# bootloader_burner.net
KiCad netlist of a schematic drawn in EAGLE
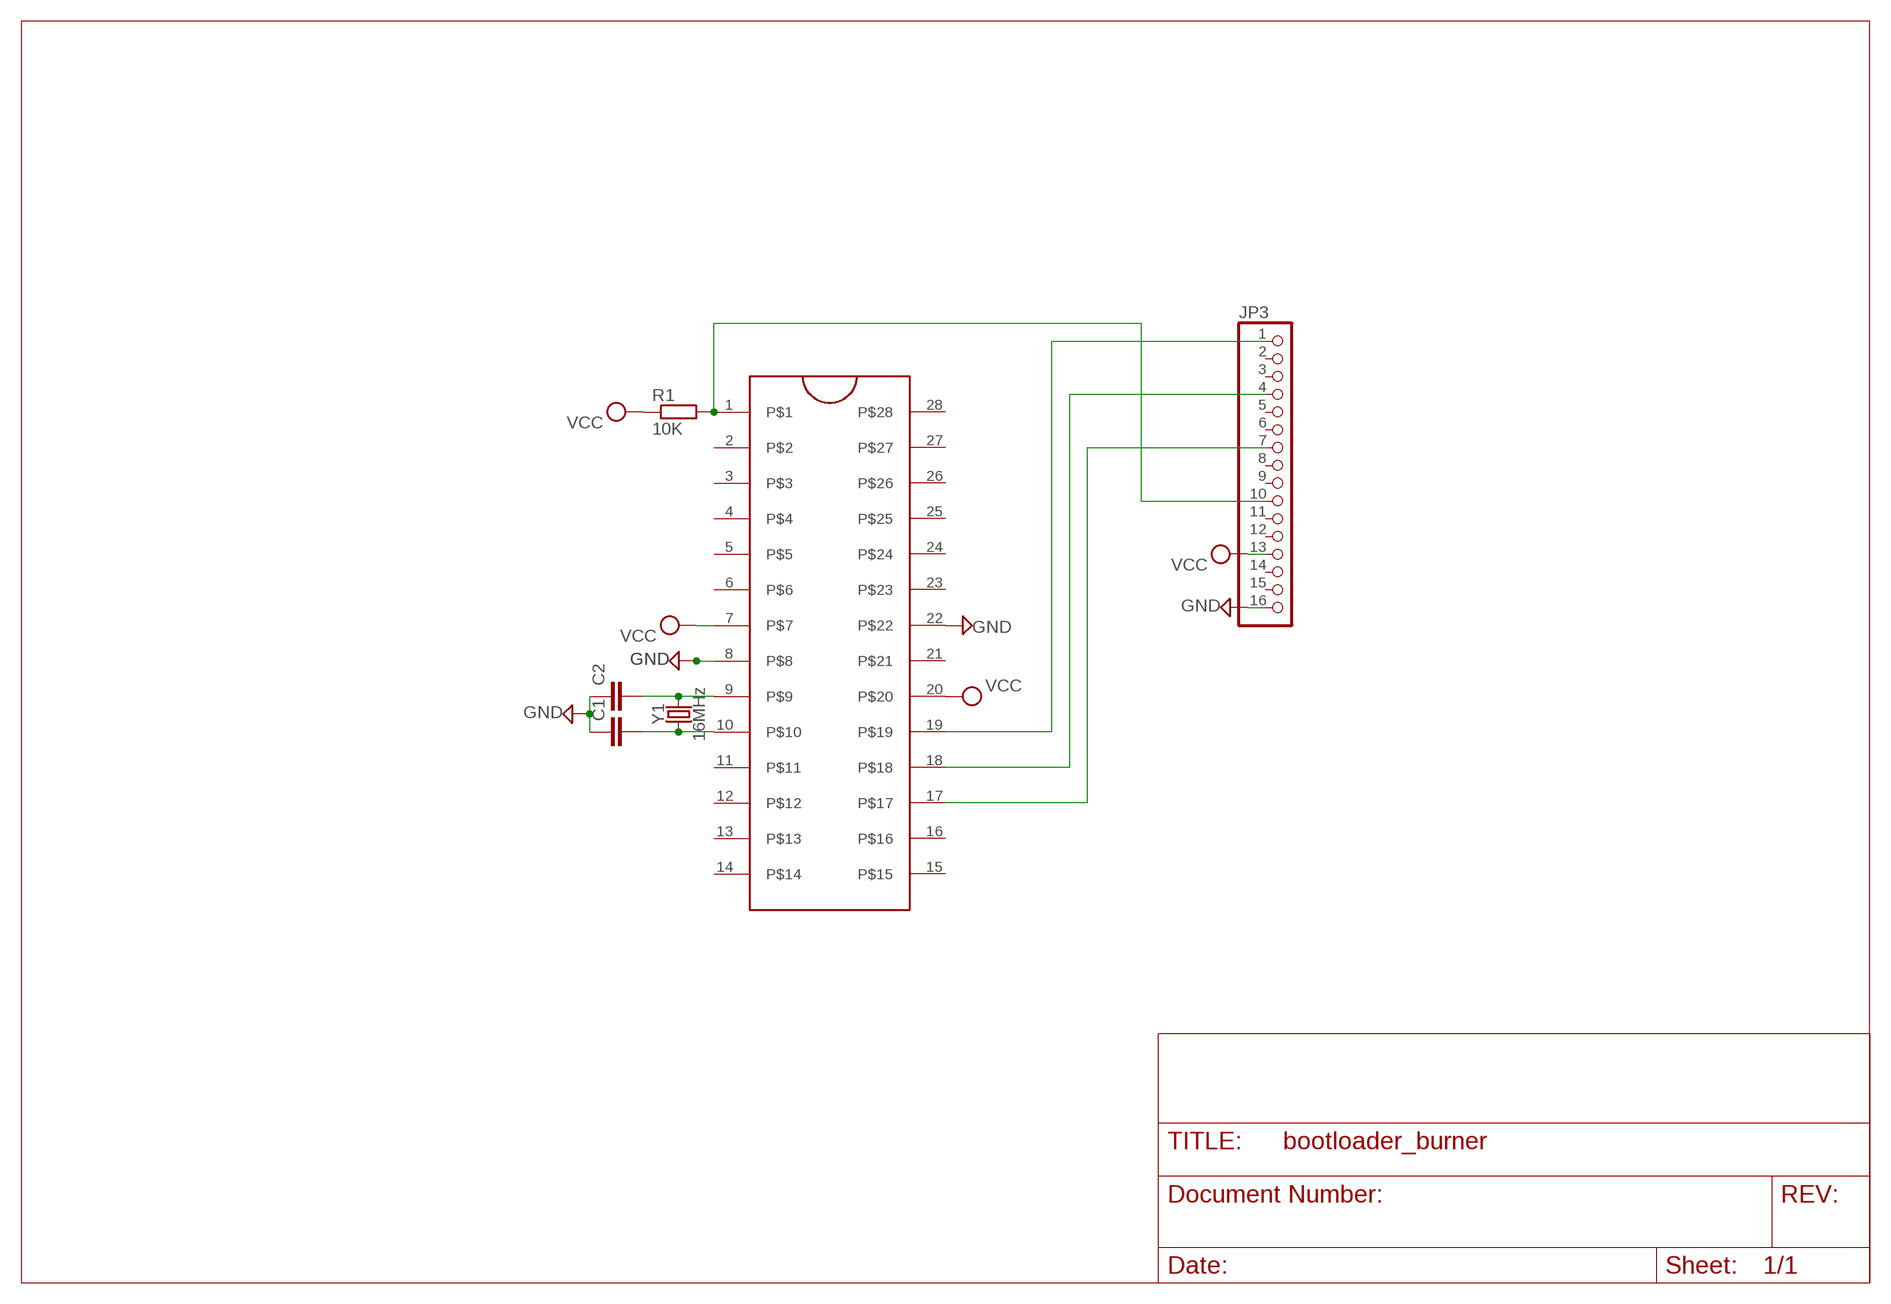
[diagram p0: schematic, sheet 1]

(export (version "E")
  (design (tool "Eeschema 10.0.6"))
  (components
    (comp (ref "C1")
      (value "C-EU050-030X075")
      (footprint "eagle-import:C050-030X075")
      (libsource (lib "eagle-import") (part "C-EU050-030X075"))
    )
    (comp (ref "C2")
      (value "C-EU050-030X075")
      (footprint "eagle-import:C050-030X075")
      (libsource (lib "eagle-import") (part "C-EU050-030X075"))
    )
    (comp (ref "J1")
      (value "ZIFSOCKET-28-3\"")
      (footprint "eagle-import:DIL28-3-ZIF_SOCKET")
      (libsource (lib "eagle-import") (part "ZIFSOCKET-28-3{dblquote}"))
    )
    (comp (ref "JP3")
      (value "PINHD-1X16")
      (footprint "eagle-import:1X16")
      (libsource (lib "eagle-import") (part "PINHD-1X16"))
    )
    (comp (ref "R1")
      (value "10K")
      (footprint "eagle-import:0207_10")
      (libsource (lib "eagle-import") (part "R-EU_0207/10"))
    )
    (comp (ref "Y1")
      (value "16MHz")
      (footprint "eagle-import:HC49US")
      (libsource (lib "eagle-import") (part "CRYSTAL-16MHZPTH-HC49US"))
    )
  )
  (nets
    (net (code "1") (name "GND") (class "Default")
      (node (ref "C1") (pin "1") (pinfunction "1_1") (pintype "passive"))
      (node (ref "C2") (pin "1") (pinfunction "1_1") (pintype "passive"))
      (node (ref "J1") (pin "22") (pinfunction "P$22_22") (pintype "bidirectional"))
      (node (ref "J1") (pin "8") (pinfunction "P$8_8") (pintype "bidirectional"))
      (node (ref "JP3") (pin "16") (pinfunction "16_16") (pintype "passive"))
    )
    (net (code "2") (name "Net-(J1-P$1)") (class "Default")
      (node (ref "J1") (pin "1") (pinfunction "P$1_1") (pintype "bidirectional"))
      (node (ref "JP3") (pin "10") (pinfunction "10_10") (pintype "passive"))
      (node (ref "R1") (pin "2") (pinfunction "2_2") (pintype "passive"))
    )
    (net (code "3") (name "Net-(J1-P$9)") (class "Default")
      (node (ref "C2") (pin "2") (pinfunction "2_2") (pintype "passive"))
      (node (ref "J1") (pin "9") (pinfunction "P$9_9") (pintype "bidirectional"))
      (node (ref "Y1") (pin "2") (pinfunction "2_2") (pintype "passive"))
    )
    (net (code "4") (name "Net-(J1-P$10)") (class "Default")
      (node (ref "C1") (pin "2") (pinfunction "2_2") (pintype "passive"))
      (node (ref "J1") (pin "10") (pinfunction "P$10_10") (pintype "bidirectional"))
      (node (ref "Y1") (pin "1") (pinfunction "1_1") (pintype "passive"))
    )
    (net (code "5") (name "Net-(J1-P$17)") (class "Default")
      (node (ref "J1") (pin "17") (pinfunction "P$17_17") (pintype "bidirectional"))
      (node (ref "JP3") (pin "7") (pinfunction "7_7") (pintype "passive"))
    )
    (net (code "6") (name "Net-(J1-P$18)") (class "Default")
      (node (ref "J1") (pin "18") (pinfunction "P$18_18") (pintype "bidirectional"))
      (node (ref "JP3") (pin "4") (pinfunction "4_4") (pintype "passive"))
    )
    (net (code "7") (name "Net-(J1-P$19)") (class "Default")
      (node (ref "J1") (pin "19") (pinfunction "P$19_19") (pintype "bidirectional"))
      (node (ref "JP3") (pin "1") (pinfunction "1_1") (pintype "passive"))
    )
    (net (code "8") (name "VCC") (class "Default")
      (node (ref "J1") (pin "20") (pinfunction "P$20_20") (pintype "bidirectional"))
      (node (ref "J1") (pin "7") (pinfunction "P$7_7") (pintype "bidirectional"))
      (node (ref "JP3") (pin "13") (pinfunction "13_13") (pintype "passive"))
      (node (ref "R1") (pin "1") (pinfunction "1_1") (pintype "passive"))
    )
    (net (code "9") (name "unconnected-(J1-P$2-Pad2)") (class "Default")
      (node (ref "J1") (pin "2") (pinfunction "P$2_2") (pintype "bidirectional"))
    )
    (net (code "10") (name "unconnected-(J1-P$3-Pad3)") (class "Default")
      (node (ref "J1") (pin "3") (pinfunction "P$3_3") (pintype "bidirectional"))
    )
    (net (code "11") (name "unconnected-(J1-P$4-Pad4)") (class "Default")
      (node (ref "J1") (pin "4") (pinfunction "P$4_4") (pintype "bidirectional"))
    )
    (net (code "12") (name "unconnected-(J1-P$5-Pad5)") (class "Default")
      (node (ref "J1") (pin "5") (pinfunction "P$5_5") (pintype "bidirectional"))
    )
    (net (code "13") (name "unconnected-(J1-P$6-Pad6)") (class "Default")
      (node (ref "J1") (pin "6") (pinfunction "P$6_6") (pintype "bidirectional"))
    )
    (net (code "14") (name "unconnected-(J1-P$11-Pad11)") (class "Default")
      (node (ref "J1") (pin "11") (pinfunction "P$11_11") (pintype "bidirectional"))
    )
    (net (code "15") (name "unconnected-(J1-P$12-Pad12)") (class "Default")
      (node (ref "J1") (pin "12") (pinfunction "P$12_12") (pintype "bidirectional"))
    )
    (net (code "16") (name "unconnected-(J1-P$13-Pad13)") (class "Default")
      (node (ref "J1") (pin "13") (pinfunction "P$13_13") (pintype "bidirectional"))
    )
    (net (code "17") (name "unconnected-(J1-P$14-Pad14)") (class "Default")
      (node (ref "J1") (pin "14") (pinfunction "P$14_14") (pintype "bidirectional"))
    )
    (net (code "18") (name "unconnected-(J1-P$15-Pad15)") (class "Default")
      (node (ref "J1") (pin "15") (pinfunction "P$15_15") (pintype "bidirectional"))
    )
    (net (code "19") (name "unconnected-(J1-P$16-Pad16)") (class "Default")
      (node (ref "J1") (pin "16") (pinfunction "P$16_16") (pintype "bidirectional"))
    )
    (net (code "20") (name "unconnected-(J1-P$21-Pad21)") (class "Default")
      (node (ref "J1") (pin "21") (pinfunction "P$21_21") (pintype "bidirectional"))
    )
    (net (code "21") (name "unconnected-(J1-P$23-Pad23)") (class "Default")
      (node (ref "J1") (pin "23") (pinfunction "P$23_23") (pintype "bidirectional"))
    )
    (net (code "22") (name "unconnected-(J1-P$24-Pad24)") (class "Default")
      (node (ref "J1") (pin "24") (pinfunction "P$24_24") (pintype "bidirectional"))
    )
    (net (code "23") (name "unconnected-(J1-P$25-Pad25)") (class "Default")
      (node (ref "J1") (pin "25") (pinfunction "P$25_25") (pintype "bidirectional"))
    )
    (net (code "24") (name "unconnected-(J1-P$26-Pad26)") (class "Default")
      (node (ref "J1") (pin "26") (pinfunction "P$26_26") (pintype "bidirectional"))
    )
    (net (code "25") (name "unconnected-(J1-P$27-Pad27)") (class "Default")
      (node (ref "J1") (pin "27") (pinfunction "P$27_27") (pintype "bidirectional"))
    )
    (net (code "26") (name "unconnected-(J1-P$28-Pad28)") (class "Default")
      (node (ref "J1") (pin "28") (pinfunction "P$28_28") (pintype "bidirectional"))
    )
    (net (code "27") (name "unconnected-(JP3-Pad2)") (class "Default")
      (node (ref "JP3") (pin "2") (pinfunction "2_2") (pintype "passive"))
    )
    (net (code "28") (name "unconnected-(JP3-Pad3)") (class "Default")
      (node (ref "JP3") (pin "3") (pinfunction "3_3") (pintype "passive"))
    )
    (net (code "29") (name "unconnected-(JP3-Pad5)") (class "Default")
      (node (ref "JP3") (pin "5") (pinfunction "5_5") (pintype "passive"))
    )
    (net (code "30") (name "unconnected-(JP3-Pad6)") (class "Default")
      (node (ref "JP3") (pin "6") (pinfunction "6_6") (pintype "passive"))
    )
    (net (code "31") (name "unconnected-(JP3-Pad8)") (class "Default")
      (node (ref "JP3") (pin "8") (pinfunction "8_8") (pintype "passive"))
    )
    (net (code "32") (name "unconnected-(JP3-Pad9)") (class "Default")
      (node (ref "JP3") (pin "9") (pinfunction "9_9") (pintype "passive"))
    )
    (net (code "33") (name "unconnected-(JP3-Pad11)") (class "Default")
      (node (ref "JP3") (pin "11") (pinfunction "11_11") (pintype "passive"))
    )
    (net (code "34") (name "unconnected-(JP3-Pad12)") (class "Default")
      (node (ref "JP3") (pin "12") (pinfunction "12_12") (pintype "passive"))
    )
    (net (code "35") (name "unconnected-(JP3-Pad14)") (class "Default")
      (node (ref "JP3") (pin "14") (pinfunction "14_14") (pintype "passive"))
    )
    (net (code "36") (name "unconnected-(JP3-Pad15)") (class "Default")
      (node (ref "JP3") (pin "15") (pinfunction "15_15") (pintype "passive"))
    )
  )
)
